# ADC_Ref.net
KiCad netlist of a schematic drawn in Altium Designer
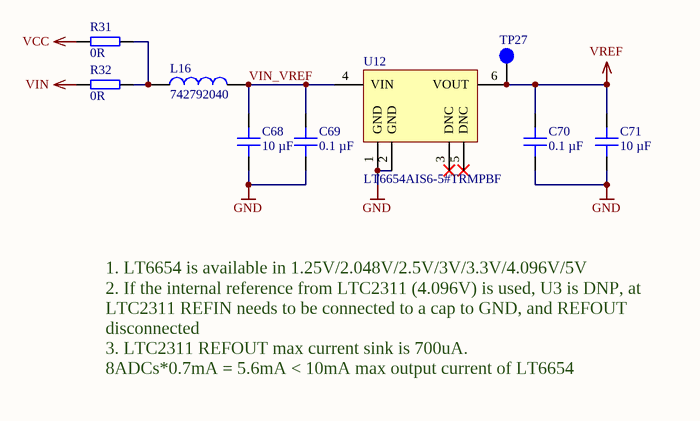
[diagram p0: ADC_Ref.SchDoc]

(export (version "E")
  (design (tool "Eeschema 10.0.6"))
  (components
    (comp (ref "C68")
      (value "10 µF")
      (footprint "C_1206")
      (description "Capacitor 1206, 35 VDC, 10 µF, X5R")
      (fields
        (field (name "MANUFACTURER PART NUMBER") "1206DD106MAT2A")
        (field (name "MANUFACTURER") "AVX")
        (field (name "CREATED FROM") "MGremer")
      )
      (libsource (lib "user") (part "Capacitor"))
    )
    (comp (ref "C69")
      (value "0.1 µF")
      (footprint "C_0603")
      (description "Capacitor 0603, 50 VDC, 0.1 µF, X7R")
      (fields
        (field (name "MANUFACTURER PART NUMBER") "C0603X104K5RAC7411")
        (field (name "MANUFACTURER") "KEMET")
        (field (name "CREATED FROM") "MGremer")
      )
      (libsource (lib "user") (part "Capacitor"))
    )
    (comp (ref "C70")
      (value "0.1 µF")
      (footprint "C_0603")
      (description "Capacitor 0603, 50 VDC, 0.1 µF, X7R")
      (fields
        (field (name "MANUFACTURER PART NUMBER") "C0603X104K5RAC7411")
        (field (name "MANUFACTURER") "KEMET")
        (field (name "CREATED FROM") "MGremer")
      )
      (libsource (lib "user") (part "Capacitor"))
    )
    (comp (ref "C71")
      (value "10 µF")
      (footprint "C_1206")
      (description "Capacitor 1206, 35 VDC, 10 µF, X5R")
      (fields
        (field (name "MANUFACTURER PART NUMBER") "1206DD106MAT2A")
        (field (name "MANUFACTURER") "AVX")
        (field (name "CREATED FROM") "MGremer")
      )
      (libsource (lib "user") (part "Capacitor"))
    )
    (comp (ref "L16")
      (value "742792040")
      (footprint "WE-CBF_0805_High Current")
      (description "Inductance, 0805, 100 MHz, 600 Ohm, 2 A")
      (fields (field (name "MANUFACTURER") "Wurth Elektronik") (field (name "CREATED FROM") "MGremer"))
      (libsource (lib "user") (part "WE-CBF"))
    )
    (comp (ref "R31")
      (value "0R")
      (footprint "RES 0603_1608")
      (description "SMD resistor E24 series")
      (fields
        (field (name "MANUFACTURER PART NUMBER") "RC0603JR-070RL")
        (field (name "MANUFACTURER") "YAGEO")
        (field (name "CREATED FROM") "MGremer")
      )
      (libsource (lib "user") (part "Resistor"))
    )
    (comp (ref "R32")
      (value "0R")
      (footprint "RES 0603_1608")
      (description "SMD resistor E24 series")
      (fields
        (field (name "MANUFACTURER PART NUMBER") "RC0603JR-070RL")
        (field (name "MANUFACTURER") "YAGEO")
        (field (name "CREATED FROM") "MGremer")
      )
      (libsource (lib "user") (part "Resistor"))
    )
    (comp (ref "TP27")
      (value "-")
      (footprint "TP_1mm")
      (description "Test Point 1 mm")
      (fields (field (name "CREATED") "2018_06_25_AGeiger") (field (name "CREATED FROM") "MGremer"))
      (libsource (lib "user") (part "TP_1mm"))
    )
    (comp (ref "U12")
      (value "LT6654AIS6-5#TRMPBF")
      (footprint "SOT95P280X100-6N")
      (description "Precision Wide Supply High Output Drive Low Noise Reference, 5 V")
      (fields (field (name "MANUFACTURER") "Analog Devices") (field (name "CREATED FROM") "MGremer"))
      (libsource (lib "user") (part "LT6654"))
    )
  )
  (nets
    (net (code "1") (name "/VIN_VREF") (class "Default")
      (node (ref "C68") (pin "2") (pinfunction "2_2") (pintype "passive"))
      (node (ref "C69") (pin "2") (pinfunction "2_2") (pintype "passive"))
      (node (ref "L16") (pin "2") (pinfunction "2_2") (pintype "passive"))
      (node (ref "U12") (pin "4") (pinfunction "VIN_4") (pintype "power_in"))
    )
    (net (code "2") (name "GND") (class "Default")
      (node (ref "C68") (pin "1") (pinfunction "1_1") (pintype "passive"))
      (node (ref "C69") (pin "1") (pinfunction "1_1") (pintype "passive"))
      (node (ref "C70") (pin "1") (pinfunction "1_1") (pintype "passive"))
      (node (ref "C71") (pin "1") (pinfunction "1_1") (pintype "passive"))
      (node (ref "U12") (pin "1") (pinfunction "GND_1") (pintype "power_in"))
      (node (ref "U12") (pin "2") (pinfunction "GND_2") (pintype "power_in"))
    )
    (net (code "3") (name "Net-(L16-Pad1)") (class "Default")
      (node (ref "L16") (pin "1") (pinfunction "1_1") (pintype "passive"))
      (node (ref "R31") (pin "2") (pinfunction "2_2") (pintype "passive"))
      (node (ref "R32") (pin "2") (pinfunction "2_2") (pintype "passive"))
    )
    (net (code "4") (name "VCC") (class "Default")
      (node (ref "R31") (pin "1") (pinfunction "1_1") (pintype "passive"))
    )
    (net (code "5") (name "VIN") (class "Default")
      (node (ref "R32") (pin "1") (pinfunction "1_1") (pintype "passive"))
    )
    (net (code "6") (name "VREF") (class "Default")
      (node (ref "C70") (pin "2") (pinfunction "2_2") (pintype "passive"))
      (node (ref "C71") (pin "2") (pinfunction "2_2") (pintype "passive"))
      (node (ref "TP27") (pin "1") (pintype "passive"))
      (node (ref "U12") (pin "6") (pinfunction "VOUT_6") (pintype "power_in"))
    )
    (net (code "7") (name "unconnected-(U12-DNC-Pad3)") (class "Default")
      (node (ref "U12") (pin "3") (pinfunction "DNC_3") (pintype "passive+no_connect"))
    )
    (net (code "8") (name "unconnected-(U12-DNC-Pad5)") (class "Default")
      (node (ref "U12") (pin "5") (pinfunction "DNC_5") (pintype "passive+no_connect"))
    )
  )
)
